# 7_M_2_Wi-Fi.net
KiCad netlist of a schematic drawn in Altium Designer
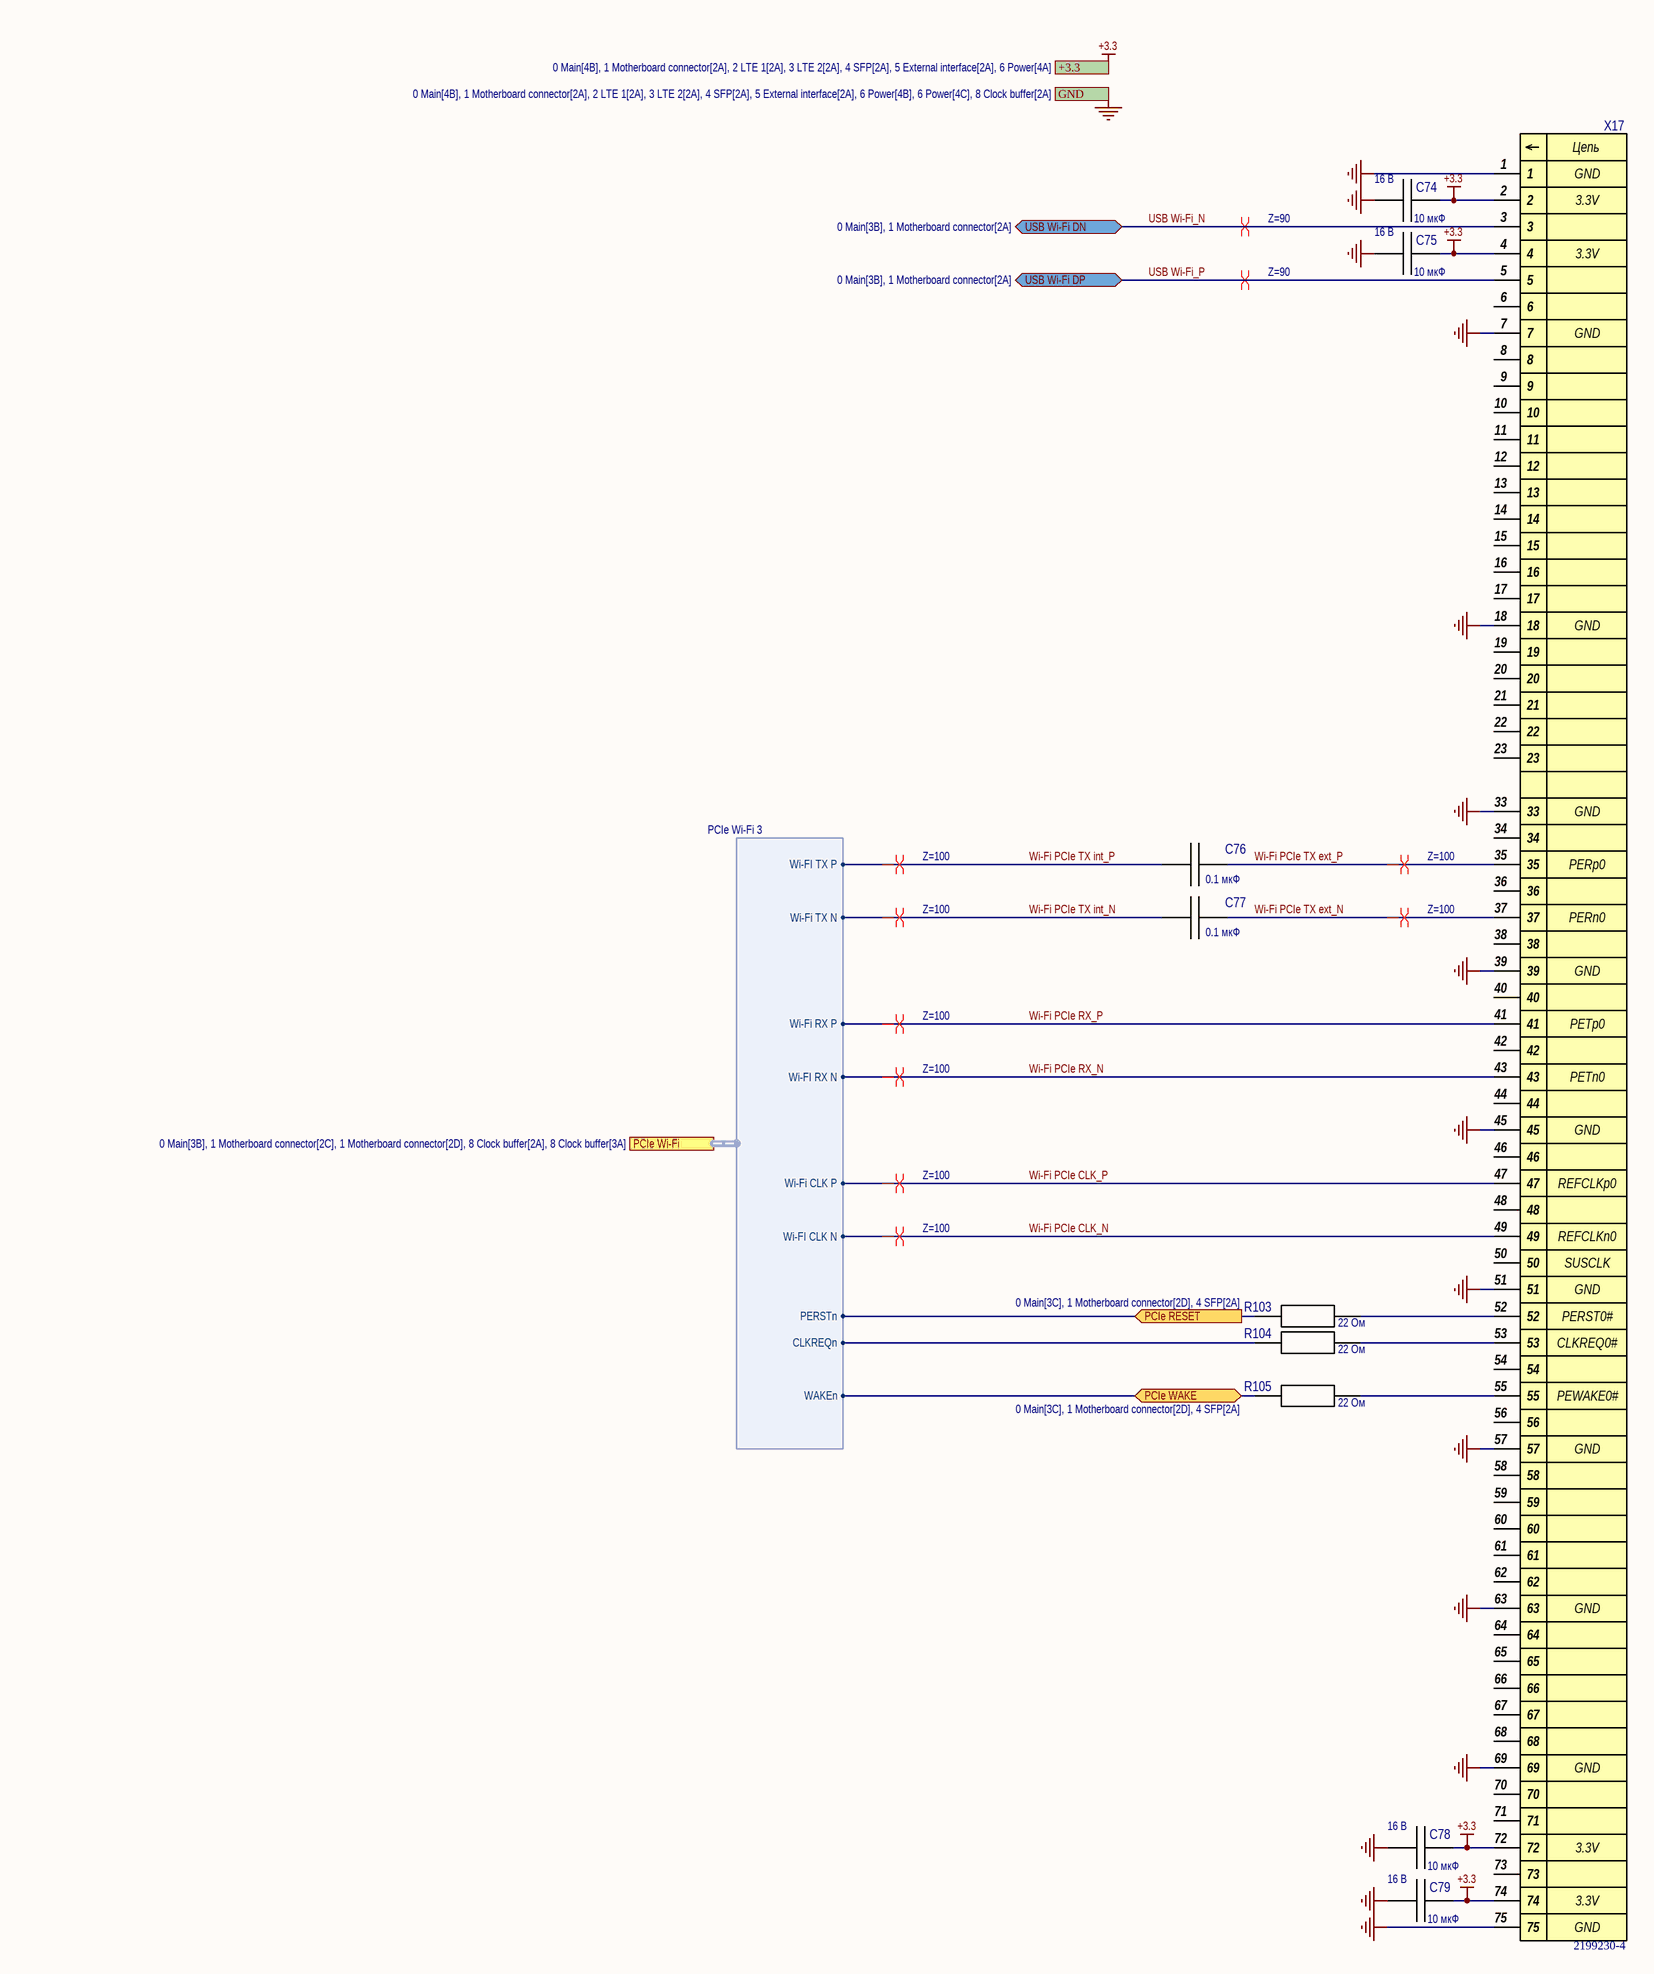
[diagram p0: 7 M.2 Wi-Fi.SchDoc]

(export (version "E")
  (design (tool "Eeschema 10.0.6"))
  (components
    (comp (ref "C74")
      (value "10 мкФ")
      (footprint "CAP_0805")
      (description "Конденсатор CHIP-0805 10 мкФ 16 В 10% X5R")
      (fields
        (field (name "PARTNUMBER") "GRM21BR61C106KE15L")
        (field (name "TOLERANCE") "10%")
        (field (name "НАПРЯЖЕНИЕ") "16 В")
        (field (name "AUTOR") "Цислав А.Н.")
      )
      (libsource (lib "Database_Altium") (part "STD_CAP"))
    )
    (comp (ref "C75")
      (value "10 мкФ")
      (footprint "CAP_0805")
      (description "Конденсатор CHIP-0805 10 мкФ 16 В 10% X5R")
      (fields
        (field (name "PARTNUMBER") "GRM21BR61C106KE15L")
        (field (name "TOLERANCE") "10%")
        (field (name "НАПРЯЖЕНИЕ") "16 В")
        (field (name "AUTOR") "Цислав А.Н.")
      )
      (libsource (lib "Database_Altium") (part "STD_CAP"))
    )
    (comp (ref "C76")
      (value "0.1 мкФ")
      (footprint "CAP_0402")
      (description "Конденсатор CHIP-0402 0.1 мкФ 25 В 10% X7R")
      (fields
        (field (name "PARTNUMBER") "GRM155R71E104KE14")
        (field (name "TOLERANCE") "10%")
        (field (name "AUTOR") "Admin")
      )
      (libsource (lib "Database_Altium") (part "STD_CAP"))
    )
    (comp (ref "C77")
      (value "0.1 мкФ")
      (footprint "CAP_0402")
      (description "Конденсатор CHIP-0402 0.1 мкФ 25 В 10% X7R")
      (fields
        (field (name "PARTNUMBER") "GRM155R71E104KE14")
        (field (name "TOLERANCE") "10%")
        (field (name "AUTOR") "Admin")
      )
      (libsource (lib "Database_Altium") (part "STD_CAP"))
    )
    (comp (ref "C78")
      (value "10 мкФ")
      (footprint "CAP_0805")
      (description "Конденсатор CHIP-0805 10 мкФ 16 В 10% X5R")
      (fields
        (field (name "PARTNUMBER") "GRM21BR61C106KE15L")
        (field (name "TOLERANCE") "10%")
        (field (name "НАПРЯЖЕНИЕ") "16 В")
        (field (name "AUTOR") "Цислав А.Н.")
      )
      (libsource (lib "Database_Altium") (part "STD_CAP"))
    )
    (comp (ref "C79")
      (value "10 мкФ")
      (footprint "CAP_0805")
      (description "Конденсатор CHIP-0805 10 мкФ 16 В 10% X5R")
      (fields
        (field (name "PARTNUMBER") "GRM21BR61C106KE15L")
        (field (name "TOLERANCE") "10%")
        (field (name "НАПРЯЖЕНИЕ") "16 В")
        (field (name "AUTOR") "Цислав А.Н.")
      )
      (libsource (lib "Database_Altium") (part "STD_CAP"))
    )
    (comp (ref "R103")
      (value "22 Ом")
      (footprint "RES_0402")
      (description "Резистор CHIP-0402 22 Ом 1%")
      (fields
        (field (name "PARTNUMBER") "RC0402FR-0722RL")
        (field (name "TOLERANCE") "1%")
        (field (name "AUTOR") "Цислав А.Н.")
      )
      (libsource (lib "Database_Altium") (part "STD_RES"))
    )
    (comp (ref "R104")
      (value "22 Ом")
      (footprint "RES_0402")
      (description "Резистор CHIP-0402 22 Ом 1%")
      (fields
        (field (name "PARTNUMBER") "RC0402FR-0722RL")
        (field (name "TOLERANCE") "1%")
        (field (name "AUTOR") "Цислав А.Н.")
      )
      (libsource (lib "Database_Altium") (part "STD_RES"))
    )
    (comp (ref "R105")
      (value "22 Ом")
      (footprint "RES_0402")
      (description "Резистор CHIP-0402 22 Ом 1%")
      (fields
        (field (name "PARTNUMBER") "RC0402FR-0722RL")
        (field (name "TOLERANCE") "1%")
        (field (name "AUTOR") "Цислав А.Н.")
      )
      (libsource (lib "Database_Altium") (part "STD_RES"))
    )
    (comp (ref "X17")
      (value "2199230-4")
      (footprint "2199230-4")
      (description "Разъем TE M.2 NGFF")
      (fields
        (field (name "PARTNUMBER") "2199230-4")
        (field (name "MANUFACTURER") "TE")
        (field (name "CONTACT") "75")
        (field (name "AUTOR") "Admin")
      )
      (libsource (lib "Database_Altium") (part "2199230-4"))
    )
  )
  (nets
    (net (code "4") (name "+3.3") (class "Default")
      (node (ref "C74") (pin "1") (pinfunction "1_1") (pintype "passive"))
      (node (ref "C75") (pin "1") (pinfunction "1_1") (pintype "passive"))
      (node (ref "C78") (pin "1") (pinfunction "1_1") (pintype "passive"))
      (node (ref "C79") (pin "1") (pinfunction "1_1") (pintype "passive"))
      (node (ref "X17") (pin "2") (pinfunction "2_2") (pintype "passive"))
      (node (ref "X17") (pin "4") (pinfunction "4_4") (pintype "passive"))
      (node (ref "X17") (pin "72") (pinfunction "72_72") (pintype "passive"))
      (node (ref "X17") (pin "74") (pinfunction "74_74") (pintype "passive"))
    )
    (net (code "5") (name "/CLKREQn") (class "Default")
      (node (ref "R104") (pin "2") (pinfunction "2_2") (pintype "passive"))
    )
    (net (code "6") (name "/PCIe RESET") (class "Default")
      (node (ref "R103") (pin "2") (pinfunction "2_2") (pintype "passive"))
    )
    (net (code "7") (name "/PCIe WAKE") (class "Default")
      (node (ref "R105") (pin "2") (pinfunction "2_2") (pintype "passive"))
    )
    (net (code "8") (name "/USB Wi-Fi_N") (class "Default")
      (node (ref "X17") (pin "3") (pinfunction "3_3") (pintype "passive"))
    )
    (net (code "9") (name "/USB Wi-Fi_P") (class "Default")
      (node (ref "X17") (pin "5") (pinfunction "5_5") (pintype "passive"))
    )
    (net (code "10") (name "/Wi-Fi PCIe CLK_N") (class "Default")
      (node (ref "X17") (pin "49") (pinfunction "49_49") (pintype "passive"))
    )
    (net (code "11") (name "/Wi-Fi PCIe CLK_P") (class "Default")
      (node (ref "X17") (pin "47") (pinfunction "47_47") (pintype "passive"))
    )
    (net (code "12") (name "/Wi-Fi PCIe RX_N") (class "Default")
      (node (ref "X17") (pin "43") (pinfunction "43_43") (pintype "passive"))
    )
    (net (code "13") (name "/Wi-Fi PCIe RX_P") (class "Default")
      (node (ref "X17") (pin "41") (pinfunction "41_41") (pintype "passive"))
    )
    (net (code "14") (name "/Wi-Fi PCIe TX ext_N") (class "Default")
      (node (ref "C77") (pin "1") (pinfunction "1_1") (pintype "passive"))
      (node (ref "X17") (pin "37") (pinfunction "37_37") (pintype "passive"))
    )
    (net (code "15") (name "/Wi-Fi PCIe TX ext_P") (class "Default")
      (node (ref "C76") (pin "1") (pinfunction "1_1") (pintype "passive"))
      (node (ref "X17") (pin "35") (pinfunction "35_35") (pintype "passive"))
    )
    (net (code "16") (name "/Wi-Fi PCIe TX int_N") (class "Default")
      (node (ref "C77") (pin "2") (pinfunction "2_2") (pintype "passive"))
    )
    (net (code "17") (name "/Wi-Fi PCIe TX int_P") (class "Default")
      (node (ref "C76") (pin "2") (pinfunction "2_2") (pintype "passive"))
    )
    (net (code "19") (name "GND") (class "Default")
      (node (ref "C74") (pin "2") (pinfunction "2_2") (pintype "passive"))
      (node (ref "C75") (pin "2") (pinfunction "2_2") (pintype "passive"))
      (node (ref "C78") (pin "2") (pinfunction "2_2") (pintype "passive"))
      (node (ref "C79") (pin "2") (pinfunction "2_2") (pintype "passive"))
      (node (ref "X17") (pin "1") (pinfunction "1_1") (pintype "passive"))
      (node (ref "X17") (pin "18") (pinfunction "18_18") (pintype "passive"))
      (node (ref "X17") (pin "33") (pinfunction "33_33") (pintype "passive"))
      (node (ref "X17") (pin "39") (pinfunction "39_39") (pintype "passive"))
      (node (ref "X17") (pin "45") (pinfunction "45_45") (pintype "passive"))
      (node (ref "X17") (pin "51") (pinfunction "51_51") (pintype "passive"))
      (node (ref "X17") (pin "57") (pinfunction "57_57") (pintype "passive"))
      (node (ref "X17") (pin "63") (pinfunction "63_63") (pintype "passive"))
      (node (ref "X17") (pin "69") (pinfunction "69_69") (pintype "passive"))
      (node (ref "X17") (pin "7") (pinfunction "7_7") (pintype "passive"))
      (node (ref "X17") (pin "75") (pinfunction "75_75") (pintype "passive"))
    )
    (net (code "20") (name "Net-(R103-Pad1)") (class "Default")
      (node (ref "R103") (pin "1") (pinfunction "1_1") (pintype "passive"))
      (node (ref "X17") (pin "52") (pinfunction "52_52") (pintype "passive"))
    )
    (net (code "21") (name "Net-(R104-Pad1)") (class "Default")
      (node (ref "R104") (pin "1") (pinfunction "1_1") (pintype "passive"))
      (node (ref "X17") (pin "53") (pinfunction "53_53") (pintype "passive"))
    )
    (net (code "22") (name "Net-(R105-Pad1)") (class "Default")
      (node (ref "R105") (pin "1") (pinfunction "1_1") (pintype "passive"))
      (node (ref "X17") (pin "55") (pinfunction "55_55") (pintype "passive"))
    )
    (net (code "23") (name "unconnected-(X17-Pad6)") (class "Default")
      (node (ref "X17") (pin "6") (pinfunction "6_6") (pintype "passive"))
    )
    (net (code "24") (name "unconnected-(X17-Pad8)") (class "Default")
      (node (ref "X17") (pin "8") (pinfunction "8_8") (pintype "passive"))
    )
    (net (code "25") (name "unconnected-(X17-Pad9)") (class "Default")
      (node (ref "X17") (pin "9") (pinfunction "9_9") (pintype "passive"))
    )
    (net (code "26") (name "unconnected-(X17-Pad10)") (class "Default")
      (node (ref "X17") (pin "10") (pinfunction "10_10") (pintype "passive"))
    )
    (net (code "27") (name "unconnected-(X17-Pad11)") (class "Default")
      (node (ref "X17") (pin "11") (pinfunction "11_11") (pintype "passive"))
    )
    (net (code "28") (name "unconnected-(X17-Pad12)") (class "Default")
      (node (ref "X17") (pin "12") (pinfunction "12_12") (pintype "passive"))
    )
    (net (code "29") (name "unconnected-(X17-Pad13)") (class "Default")
      (node (ref "X17") (pin "13") (pinfunction "13_13") (pintype "passive"))
    )
    (net (code "30") (name "unconnected-(X17-Pad14)") (class "Default")
      (node (ref "X17") (pin "14") (pinfunction "14_14") (pintype "passive"))
    )
    (net (code "31") (name "unconnected-(X17-Pad15)") (class "Default")
      (node (ref "X17") (pin "15") (pinfunction "15_15") (pintype "passive"))
    )
    (net (code "32") (name "unconnected-(X17-Pad16)") (class "Default")
      (node (ref "X17") (pin "16") (pinfunction "16_16") (pintype "passive"))
    )
    (net (code "33") (name "unconnected-(X17-Pad17)") (class "Default")
      (node (ref "X17") (pin "17") (pinfunction "17_17") (pintype "passive"))
    )
    (net (code "34") (name "unconnected-(X17-Pad19)") (class "Default")
      (node (ref "X17") (pin "19") (pinfunction "19_19") (pintype "passive"))
    )
    (net (code "35") (name "unconnected-(X17-Pad20)") (class "Default")
      (node (ref "X17") (pin "20") (pinfunction "20_20") (pintype "passive"))
    )
    (net (code "36") (name "unconnected-(X17-Pad21)") (class "Default")
      (node (ref "X17") (pin "21") (pinfunction "21_21") (pintype "passive"))
    )
    (net (code "37") (name "unconnected-(X17-Pad22)") (class "Default")
      (node (ref "X17") (pin "22") (pinfunction "22_22") (pintype "passive"))
    )
    (net (code "38") (name "unconnected-(X17-Pad23)") (class "Default")
      (node (ref "X17") (pin "23") (pinfunction "23_23") (pintype "passive"))
    )
    (net (code "39") (name "unconnected-(X17-Pad34)") (class "Default")
      (node (ref "X17") (pin "34") (pinfunction "34_34") (pintype "passive"))
    )
    (net (code "40") (name "unconnected-(X17-Pad36)") (class "Default")
      (node (ref "X17") (pin "36") (pinfunction "36_36") (pintype "passive"))
    )
    (net (code "41") (name "unconnected-(X17-Pad38)") (class "Default")
      (node (ref "X17") (pin "38") (pinfunction "38_38") (pintype "passive"))
    )
    (net (code "42") (name "unconnected-(X17-Pad40)") (class "Default")
      (node (ref "X17") (pin "40") (pinfunction "40_40") (pintype "passive"))
    )
    (net (code "43") (name "unconnected-(X17-Pad42)") (class "Default")
      (node (ref "X17") (pin "42") (pinfunction "42_42") (pintype "passive"))
    )
    (net (code "44") (name "unconnected-(X17-Pad44)") (class "Default")
      (node (ref "X17") (pin "44") (pinfunction "44_44") (pintype "passive"))
    )
    (net (code "45") (name "unconnected-(X17-Pad46)") (class "Default")
      (node (ref "X17") (pin "46") (pinfunction "46_46") (pintype "passive"))
    )
    (net (code "46") (name "unconnected-(X17-Pad48)") (class "Default")
      (node (ref "X17") (pin "48") (pinfunction "48_48") (pintype "passive"))
    )
    (net (code "47") (name "unconnected-(X17-Pad50)") (class "Default")
      (node (ref "X17") (pin "50") (pinfunction "50_50") (pintype "passive"))
    )
    (net (code "48") (name "unconnected-(X17-Pad54)") (class "Default")
      (node (ref "X17") (pin "54") (pinfunction "54_54") (pintype "passive"))
    )
    (net (code "49") (name "unconnected-(X17-Pad56)") (class "Default")
      (node (ref "X17") (pin "56") (pinfunction "56_56") (pintype "passive"))
    )
    (net (code "50") (name "unconnected-(X17-Pad58)") (class "Default")
      (node (ref "X17") (pin "58") (pinfunction "58_58") (pintype "passive"))
    )
    (net (code "51") (name "unconnected-(X17-Pad59)") (class "Default")
      (node (ref "X17") (pin "59") (pinfunction "59_59") (pintype "passive"))
    )
    (net (code "52") (name "unconnected-(X17-Pad60)") (class "Default")
      (node (ref "X17") (pin "60") (pinfunction "60_60") (pintype "passive"))
    )
    (net (code "53") (name "unconnected-(X17-Pad61)") (class "Default")
      (node (ref "X17") (pin "61") (pinfunction "61_61") (pintype "passive"))
    )
    (net (code "54") (name "unconnected-(X17-Pad62)") (class "Default")
      (node (ref "X17") (pin "62") (pinfunction "62_62") (pintype "passive"))
    )
    (net (code "55") (name "unconnected-(X17-Pad64)") (class "Default")
      (node (ref "X17") (pin "64") (pinfunction "64_64") (pintype "passive"))
    )
    (net (code "56") (name "unconnected-(X17-Pad65)") (class "Default")
      (node (ref "X17") (pin "65") (pinfunction "65_65") (pintype "passive"))
    )
    (net (code "57") (name "unconnected-(X17-Pad66)") (class "Default")
      (node (ref "X17") (pin "66") (pinfunction "66_66") (pintype "passive"))
    )
    (net (code "58") (name "unconnected-(X17-Pad67)") (class "Default")
      (node (ref "X17") (pin "67") (pinfunction "67_67") (pintype "passive"))
    )
    (net (code "59") (name "unconnected-(X17-Pad68)") (class "Default")
      (node (ref "X17") (pin "68") (pinfunction "68_68") (pintype "passive"))
    )
    (net (code "60") (name "unconnected-(X17-Pad70)") (class "Default")
      (node (ref "X17") (pin "70") (pinfunction "70_70") (pintype "passive"))
    )
    (net (code "61") (name "unconnected-(X17-Pad71)") (class "Default")
      (node (ref "X17") (pin "71") (pinfunction "71_71") (pintype "passive"))
    )
    (net (code "62") (name "unconnected-(X17-Pad73)") (class "Default")
      (node (ref "X17") (pin "73") (pinfunction "73_73") (pintype "passive"))
    )
  )
)
